# euclidean.net
KiCad netlist of a schematic drawn in EAGLE
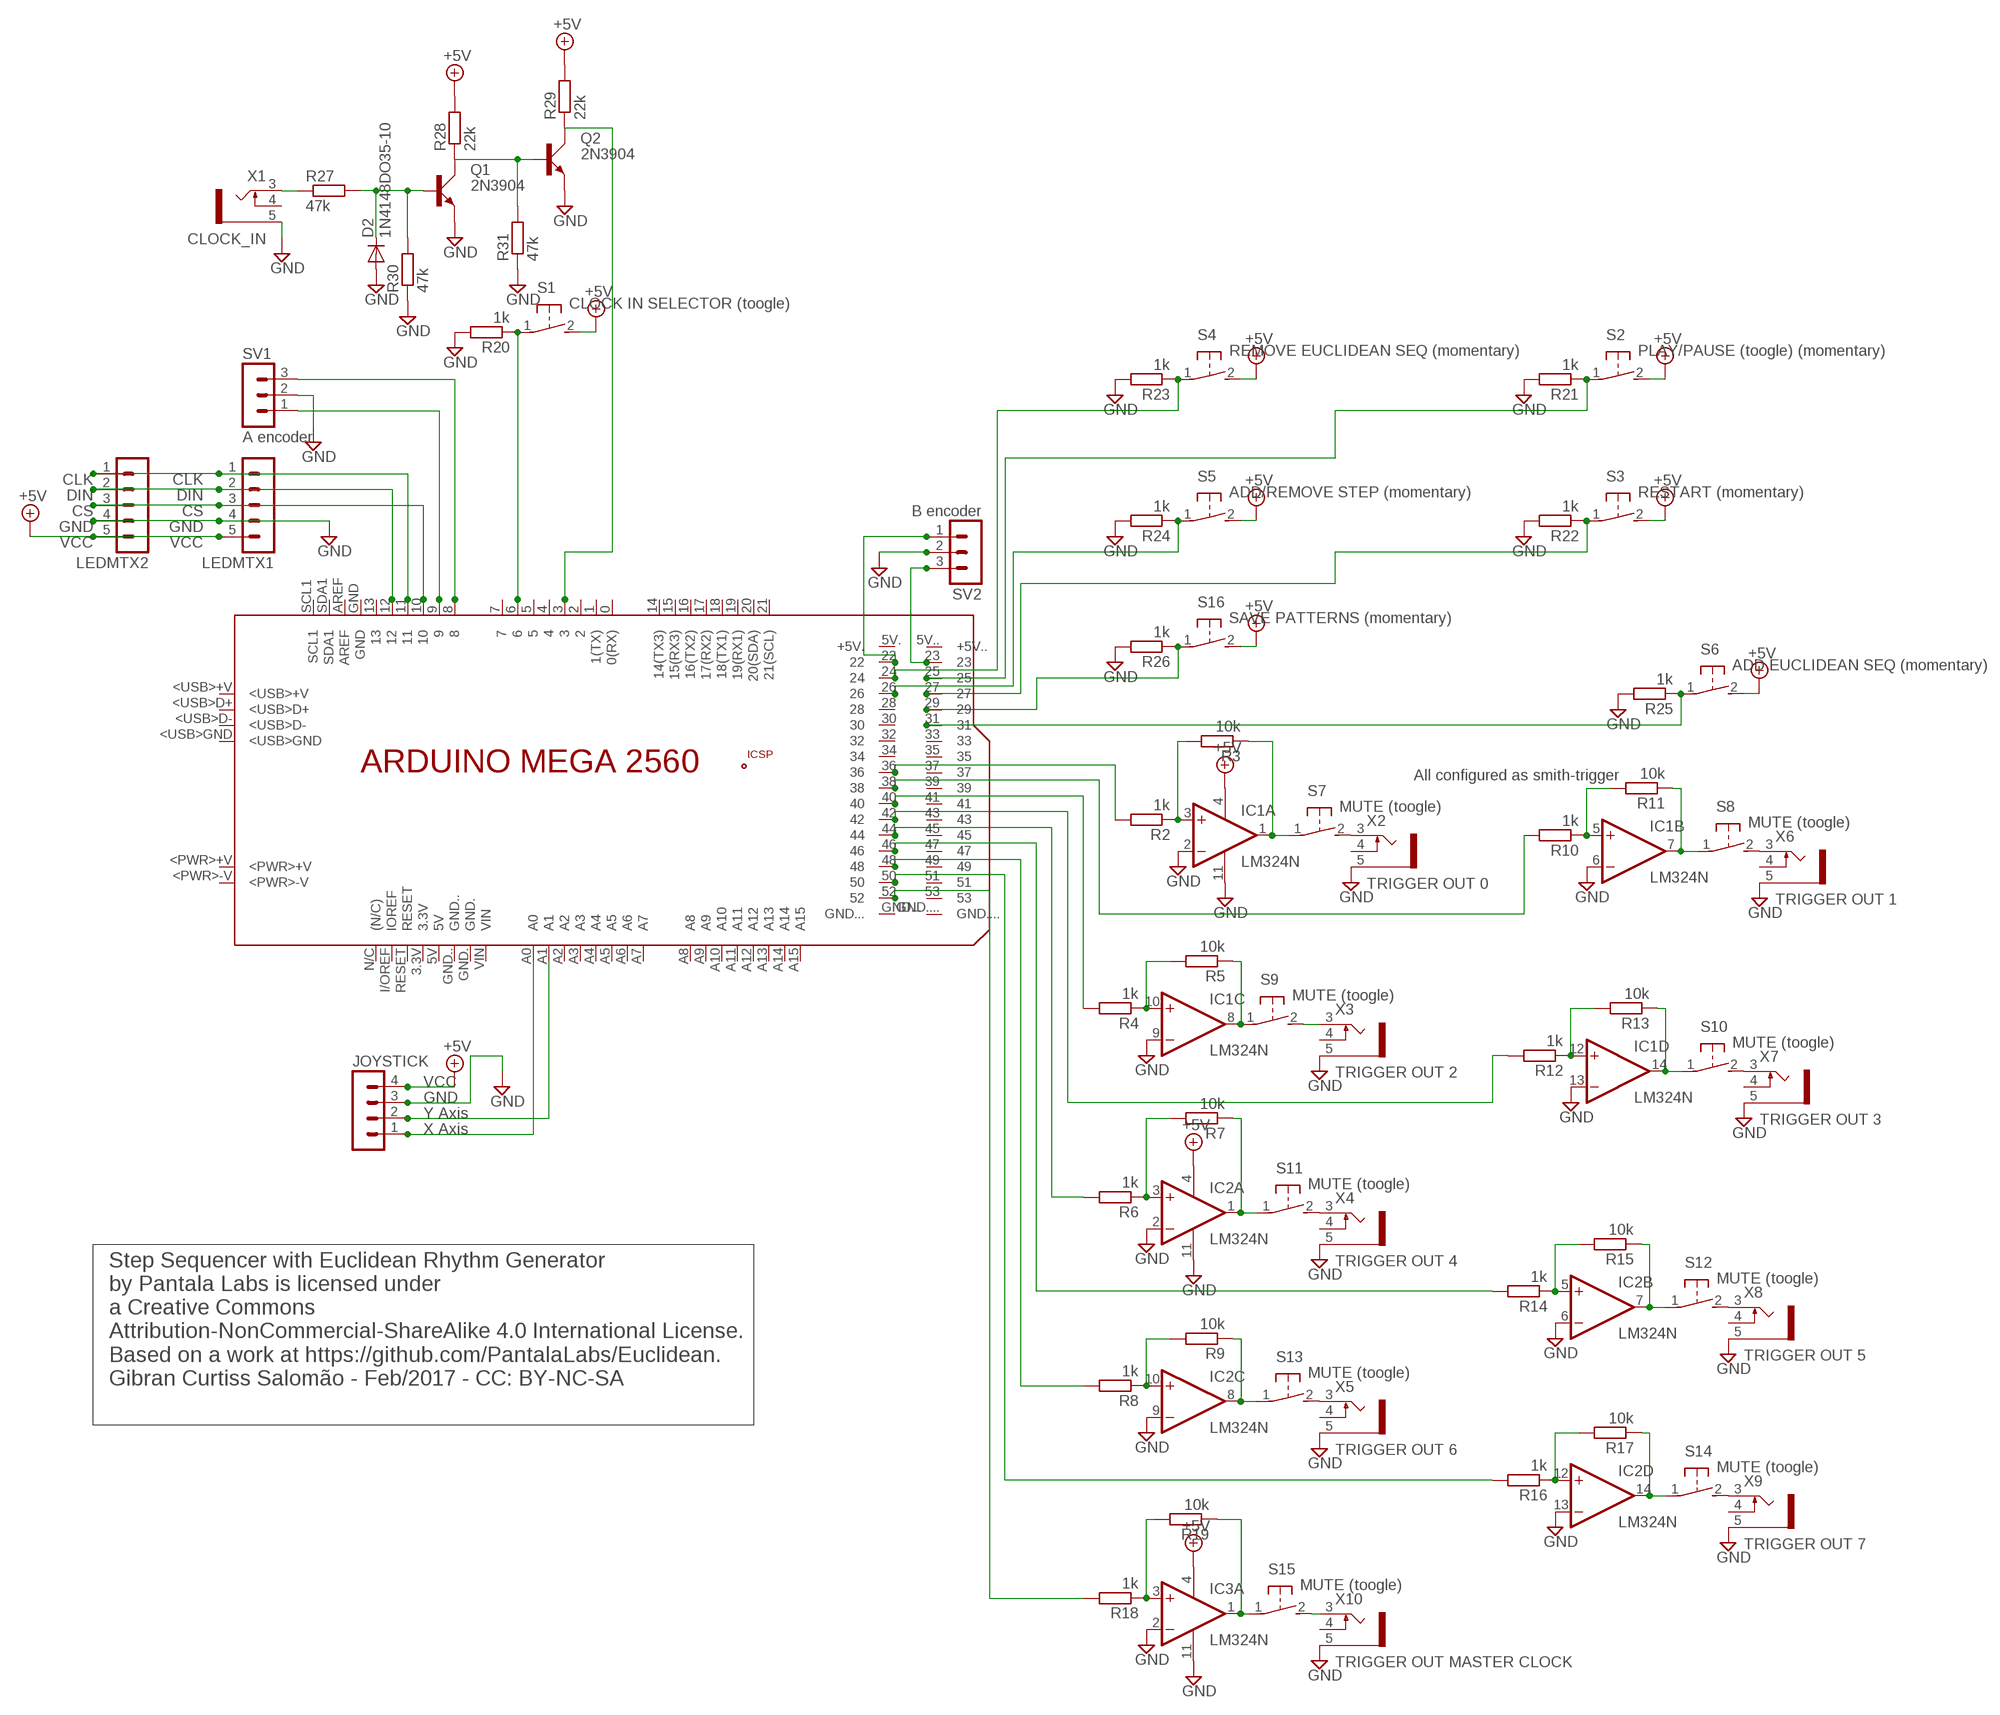
[diagram p0: schematic, sheet 1]

(export (version "E")
  (design (tool "Eeschema 10.0.6"))
  (components
    (comp (ref "D2")
      (value "1N4148DO35-10")
      (footprint "eagle-import:DO35-10")
      (libsource (lib "eagle-import") (part "1N4148DO35-10"))
    )
    (comp (ref "IC1")
      (value "LM324N")
      (footprint "eagle-import:DIL14")
      (libsource (lib "eagle-import") (part "LM324N"))
    )
    (comp (ref "IC2")
      (value "LM324N")
      (footprint "eagle-import:DIL14")
      (libsource (lib "eagle-import") (part "LM324N"))
    )
    (comp (ref "IC3")
      (value "LM324N")
      (footprint "eagle-import:DIL14")
      (libsource (lib "eagle-import") (part "LM324N"))
    )
    (comp (ref "JOYSTICK")
      (value "MA04-1")
      (footprint "eagle-import:MA04-1")
      (libsource (lib "eagle-import") (part "MA04-1"))
    )
    (comp (ref "LEDMTX1")
      (value "MA05-1")
      (footprint "eagle-import:MA05-1")
      (libsource (lib "eagle-import") (part "MA05-1"))
    )
    (comp (ref "LEDMTX2")
      (value "MA05-1")
      (footprint "eagle-import:MA05-1")
      (libsource (lib "eagle-import") (part "MA05-1"))
    )
    (comp (ref "PCB1")
      (value "ARDUINO_MEGA2560")
      (footprint "eagle-import:ARDUINO_MEGA2560")
      (libsource (lib "eagle-import") (part "ARDUINO_MEGA2560"))
    )
    (comp (ref "Q1")
      (value "2N3904")
      (footprint "eagle-import:TO92D")
      (libsource (lib "eagle-import") (part "2N3904"))
    )
    (comp (ref "Q2")
      (value "2N3904")
      (footprint "eagle-import:TO92D")
      (libsource (lib "eagle-import") (part "2N3904"))
    )
    (comp (ref "R2")
      (value "1k")
      (footprint "eagle-import:0204_7")
      (libsource (lib "eagle-import") (part "R-EU_0204/7"))
    )
    (comp (ref "R3")
      (value "10k")
      (footprint "eagle-import:0204_7")
      (libsource (lib "eagle-import") (part "R-EU_0204/7"))
    )
    (comp (ref "R4")
      (value "1k")
      (footprint "eagle-import:0204_7")
      (libsource (lib "eagle-import") (part "R-EU_0204/7"))
    )
    (comp (ref "R5")
      (value "10k")
      (footprint "eagle-import:0204_7")
      (libsource (lib "eagle-import") (part "R-EU_0204/7"))
    )
    (comp (ref "R6")
      (value "1k")
      (footprint "eagle-import:0204_7")
      (libsource (lib "eagle-import") (part "R-EU_0204/7"))
    )
    (comp (ref "R7")
      (value "10k")
      (footprint "eagle-import:0204_7")
      (libsource (lib "eagle-import") (part "R-EU_0204/7"))
    )
    (comp (ref "R8")
      (value "1k")
      (footprint "eagle-import:0204_7")
      (libsource (lib "eagle-import") (part "R-EU_0204/7"))
    )
    (comp (ref "R9")
      (value "10k")
      (footprint "eagle-import:0204_7")
      (libsource (lib "eagle-import") (part "R-EU_0204/7"))
    )
    (comp (ref "R10")
      (value "1k")
      (footprint "eagle-import:0204_7")
      (libsource (lib "eagle-import") (part "R-EU_0204/7"))
    )
    (comp (ref "R11")
      (value "10k")
      (footprint "eagle-import:0204_7")
      (libsource (lib "eagle-import") (part "R-EU_0204/7"))
    )
    (comp (ref "R12")
      (value "1k")
      (footprint "eagle-import:0204_7")
      (libsource (lib "eagle-import") (part "R-EU_0204/7"))
    )
    (comp (ref "R13")
      (value "10k")
      (footprint "eagle-import:0204_7")
      (libsource (lib "eagle-import") (part "R-EU_0204/7"))
    )
    (comp (ref "R14")
      (value "1k")
      (footprint "eagle-import:0204_7")
      (libsource (lib "eagle-import") (part "R-EU_0204/7"))
    )
    (comp (ref "R15")
      (value "10k")
      (footprint "eagle-import:0204_7")
      (libsource (lib "eagle-import") (part "R-EU_0204/7"))
    )
    (comp (ref "R16")
      (value "1k")
      (footprint "eagle-import:0204_7")
      (libsource (lib "eagle-import") (part "R-EU_0204/7"))
    )
    (comp (ref "R17")
      (value "10k")
      (footprint "eagle-import:0204_7")
      (libsource (lib "eagle-import") (part "R-EU_0204/7"))
    )
    (comp (ref "R18")
      (value "1k")
      (footprint "eagle-import:0204_7")
      (libsource (lib "eagle-import") (part "R-EU_0204/7"))
    )
    (comp (ref "R19")
      (value "10k")
      (footprint "eagle-import:0204_7")
      (libsource (lib "eagle-import") (part "R-EU_0204/7"))
    )
    (comp (ref "R20")
      (value "1k")
      (footprint "eagle-import:0204_7")
      (libsource (lib "eagle-import") (part "R-EU_0204/7"))
    )
    (comp (ref "R21")
      (value "1k")
      (footprint "eagle-import:0204_7")
      (libsource (lib "eagle-import") (part "R-EU_0204/7"))
    )
    (comp (ref "R22")
      (value "1k")
      (footprint "eagle-import:0204_7")
      (libsource (lib "eagle-import") (part "R-EU_0204/7"))
    )
    (comp (ref "R23")
      (value "1k")
      (footprint "eagle-import:0204_7")
      (libsource (lib "eagle-import") (part "R-EU_0204/7"))
    )
    (comp (ref "R24")
      (value "1k")
      (footprint "eagle-import:0204_7")
      (libsource (lib "eagle-import") (part "R-EU_0204/7"))
    )
    (comp (ref "R25")
      (value "1k")
      (footprint "eagle-import:0204_7")
      (libsource (lib "eagle-import") (part "R-EU_0204/7"))
    )
    (comp (ref "R26")
      (value "1k")
      (footprint "eagle-import:0204_7")
      (libsource (lib "eagle-import") (part "R-EU_0204/7"))
    )
    (comp (ref "R27")
      (value "47k")
      (footprint "eagle-import:0204_7")
      (libsource (lib "eagle-import") (part "R-EU_0204/7"))
    )
    (comp (ref "R28")
      (value "22k")
      (footprint "eagle-import:0204_7")
      (libsource (lib "eagle-import") (part "R-EU_0204/7"))
    )
    (comp (ref "R29")
      (value "22k")
      (footprint "eagle-import:0204_7")
      (libsource (lib "eagle-import") (part "R-EU_0204/7"))
    )
    (comp (ref "R30")
      (value "47k")
      (footprint "eagle-import:0204_7")
      (libsource (lib "eagle-import") (part "R-EU_0204/7"))
    )
    (comp (ref "R31")
      (value "47k")
      (footprint "eagle-import:0204_7")
      (libsource (lib "eagle-import") (part "R-EU_0204/7"))
    )
    (comp (ref "S1")
      (value "CLOCK IN SELECTOR (toogle)")
      (footprint "eagle-import:B3F-31XX")
      (fields (field (name "MPN") "B3F-3100"))
      (libsource (lib "eagle-import") (part "31-XX"))
    )
    (comp (ref "S2")
      (value "PLAY/PAUSE (toogle) (momentary)")
      (footprint "eagle-import:B3F-31XX")
      (fields (field (name "MPN") "B3F-3100"))
      (libsource (lib "eagle-import") (part "31-XX"))
    )
    (comp (ref "S3")
      (value "RESTART (momentary)")
      (footprint "eagle-import:B3F-31XX")
      (fields (field (name "MPN") "B3F-3100"))
      (libsource (lib "eagle-import") (part "31-XX"))
    )
    (comp (ref "S4")
      (value "REMOVE EUCLIDEAN SEQ (momentary)")
      (footprint "eagle-import:B3F-31XX")
      (fields (field (name "MPN") "B3F-3100"))
      (libsource (lib "eagle-import") (part "31-XX"))
    )
    (comp (ref "S5")
      (value "ADD/REMOVE STEP (momentary)")
      (footprint "eagle-import:B3F-31XX")
      (fields (field (name "MPN") "B3F-3100"))
      (libsource (lib "eagle-import") (part "31-XX"))
    )
    (comp (ref "S6")
      (value "ADD EUCLIDEAN SEQ (momentary)")
      (footprint "eagle-import:B3F-31XX")
      (fields (field (name "MPN") "B3F-3100"))
      (libsource (lib "eagle-import") (part "31-XX"))
    )
    (comp (ref "S7")
      (value "MUTE (toogle)")
      (footprint "eagle-import:B3F-31XX")
      (fields (field (name "MPN") "B3F-3100"))
      (libsource (lib "eagle-import") (part "31-XX"))
    )
    (comp (ref "S8")
      (value "MUTE (toogle)")
      (footprint "eagle-import:B3F-31XX")
      (fields (field (name "MPN") "B3F-3100"))
      (libsource (lib "eagle-import") (part "31-XX"))
    )
    (comp (ref "S9")
      (value "MUTE (toogle)")
      (footprint "eagle-import:B3F-31XX")
      (fields (field (name "MPN") "B3F-3100"))
      (libsource (lib "eagle-import") (part "31-XX"))
    )
    (comp (ref "S10")
      (value "MUTE (toogle)")
      (footprint "eagle-import:B3F-31XX")
      (fields (field (name "MPN") "B3F-3100"))
      (libsource (lib "eagle-import") (part "31-XX"))
    )
    (comp (ref "S11")
      (value "MUTE (toogle)")
      (footprint "eagle-import:B3F-31XX")
      (fields (field (name "MPN") "B3F-3100"))
      (libsource (lib "eagle-import") (part "31-XX"))
    )
    (comp (ref "S12")
      (value "MUTE (toogle)")
      (footprint "eagle-import:B3F-31XX")
      (fields (field (name "MPN") "B3F-3100"))
      (libsource (lib "eagle-import") (part "31-XX"))
    )
    (comp (ref "S13")
      (value "MUTE (toogle)")
      (footprint "eagle-import:B3F-31XX")
      (fields (field (name "MPN") "B3F-3100"))
      (libsource (lib "eagle-import") (part "31-XX"))
    )
    (comp (ref "S14")
      (value "MUTE (toogle)")
      (footprint "eagle-import:B3F-31XX")
      (fields (field (name "MPN") "B3F-3100"))
      (libsource (lib "eagle-import") (part "31-XX"))
    )
    (comp (ref "S15")
      (value "MUTE (toogle)")
      (footprint "eagle-import:B3F-31XX")
      (fields (field (name "MPN") "B3F-3100"))
      (libsource (lib "eagle-import") (part "31-XX"))
    )
    (comp (ref "S16")
      (value "SAVE PATTERNS (momentary)")
      (footprint "eagle-import:B3F-31XX")
      (fields (field (name "MPN") "B3F-3100"))
      (libsource (lib "eagle-import") (part "31-XX"))
    )
    (comp (ref "SV1")
      (value "A encoder")
      (footprint "eagle-import:MA03-1")
      (libsource (lib "eagle-import") (part "MA03-1"))
    )
    (comp (ref "SV2")
      (value "B encoder")
      (footprint "eagle-import:MA03-1")
      (libsource (lib "eagle-import") (part "MA03-1"))
    )
    (comp (ref "X1")
      (value "CLOCK_IN")
      (footprint "eagle-import:KLBR1")
      (fields (field (name "MPN") "KLBR 1"))
      (libsource (lib "eagle-import") (part "KLBR?1"))
    )
    (comp (ref "X2")
      (value "TRIGGER OUT 0")
      (footprint "eagle-import:KLBR1")
      (fields (field (name "MPN") "KLBR 1"))
      (libsource (lib "eagle-import") (part "KLBR?1"))
    )
    (comp (ref "X3")
      (value "TRIGGER OUT 2")
      (footprint "eagle-import:KLBR1")
      (fields (field (name "MPN") "KLBR 1"))
      (libsource (lib "eagle-import") (part "KLBR?1"))
    )
    (comp (ref "X4")
      (value "TRIGGER OUT 4")
      (footprint "eagle-import:KLBR1")
      (fields (field (name "MPN") "KLBR 1"))
      (libsource (lib "eagle-import") (part "KLBR?1"))
    )
    (comp (ref "X5")
      (value "TRIGGER OUT 6")
      (footprint "eagle-import:KLBR1")
      (fields (field (name "MPN") "KLBR 1"))
      (libsource (lib "eagle-import") (part "KLBR?1"))
    )
    (comp (ref "X6")
      (value "TRIGGER OUT 1")
      (footprint "eagle-import:KLBR1")
      (fields (field (name "MPN") "KLBR 1"))
      (libsource (lib "eagle-import") (part "KLBR?1"))
    )
    (comp (ref "X7")
      (value "TRIGGER OUT 3")
      (footprint "eagle-import:KLBR1")
      (fields (field (name "MPN") "KLBR 1"))
      (libsource (lib "eagle-import") (part "KLBR?1"))
    )
    (comp (ref "X8")
      (value "TRIGGER OUT 5")
      (footprint "eagle-import:KLBR1")
      (fields (field (name "MPN") "KLBR 1"))
      (libsource (lib "eagle-import") (part "KLBR?1"))
    )
    (comp (ref "X9")
      (value "TRIGGER OUT 7")
      (footprint "eagle-import:KLBR1")
      (fields (field (name "MPN") "KLBR 1"))
      (libsource (lib "eagle-import") (part "KLBR?1"))
    )
    (comp (ref "X10")
      (value "TRIGGER OUT MASTER CLOCK")
      (footprint "eagle-import:KLBR1")
      (fields (field (name "MPN") "KLBR 1"))
      (libsource (lib "eagle-import") (part "KLBR?1"))
    )
  )
  (nets
    (net (code "1") (name "+5V") (class "Default")
      (node (ref "IC1") (pin "4") (pinfunction "V+_4") (pintype "power_in"))
      (node (ref "IC2") (pin "4") (pinfunction "V+_4") (pintype "power_in"))
      (node (ref "IC3") (pin "4") (pinfunction "V+_4") (pintype "power_in"))
      (node (ref "JOYSTICK") (pin "4") (pinfunction "4_4") (pintype "passive"))
      (node (ref "LEDMTX1") (pin "5") (pinfunction "5_5") (pintype "passive"))
      (node (ref "LEDMTX2") (pin "5") (pinfunction "5_5") (pintype "passive"))
      (node (ref "R28") (pin "2") (pinfunction "2_2") (pintype "passive"))
      (node (ref "R29") (pin "2") (pinfunction "2_2") (pintype "passive"))
      (node (ref "S1") (pin "2") (pinfunction "S_2") (pintype "passive"))
      (node (ref "S16") (pin "2") (pinfunction "S_2") (pintype "passive"))
      (node (ref "S2") (pin "2") (pinfunction "S_2") (pintype "passive"))
      (node (ref "S3") (pin "2") (pinfunction "S_2") (pintype "passive"))
      (node (ref "S4") (pin "2") (pinfunction "S_2") (pintype "passive"))
      (node (ref "S5") (pin "2") (pinfunction "S_2") (pintype "passive"))
      (node (ref "S6") (pin "2") (pinfunction "S_2") (pintype "passive"))
    )
    (net (code "2") (name "GND") (class "Default")
      (node (ref "D2") (pin "A") (pinfunction "A_A") (pintype "passive"))
      (node (ref "IC1") (pin "11") (pinfunction "V-_11") (pintype "power_in"))
      (node (ref "IC1") (pin "13") (pinfunction "-IN_13") (pintype "input"))
      (node (ref "IC1") (pin "2") (pinfunction "-IN_2") (pintype "input"))
      (node (ref "IC1") (pin "6") (pinfunction "-IN_6") (pintype "input"))
      (node (ref "IC1") (pin "9") (pinfunction "-IN_9") (pintype "input"))
      (node (ref "IC2") (pin "11") (pinfunction "V-_11") (pintype "power_in"))
      (node (ref "IC2") (pin "13") (pinfunction "-IN_13") (pintype "input"))
      (node (ref "IC2") (pin "2") (pinfunction "-IN_2") (pintype "input"))
      (node (ref "IC2") (pin "6") (pinfunction "-IN_6") (pintype "input"))
      (node (ref "IC2") (pin "9") (pinfunction "-IN_9") (pintype "input"))
      (node (ref "IC3") (pin "11") (pinfunction "V-_11") (pintype "power_in"))
      (node (ref "IC3") (pin "2") (pinfunction "-IN_2") (pintype "input"))
      (node (ref "JOYSTICK") (pin "3") (pinfunction "3_3") (pintype "passive"))
      (node (ref "LEDMTX1") (pin "4") (pinfunction "4_4") (pintype "passive"))
      (node (ref "LEDMTX2") (pin "4") (pinfunction "4_4") (pintype "passive"))
      (node (ref "Q1") (pin "E") (pinfunction "E_E") (pintype "passive"))
      (node (ref "Q2") (pin "E") (pinfunction "E_E") (pintype "passive"))
      (node (ref "R20") (pin "2") (pinfunction "2_2") (pintype "passive"))
      (node (ref "R21") (pin "2") (pinfunction "2_2") (pintype "passive"))
      (node (ref "R22") (pin "2") (pinfunction "2_2") (pintype "passive"))
      (node (ref "R23") (pin "2") (pinfunction "2_2") (pintype "passive"))
      (node (ref "R24") (pin "2") (pinfunction "2_2") (pintype "passive"))
      (node (ref "R25") (pin "2") (pinfunction "2_2") (pintype "passive"))
      (node (ref "R26") (pin "2") (pinfunction "2_2") (pintype "passive"))
      (node (ref "R30") (pin "1") (pinfunction "1_1") (pintype "passive"))
      (node (ref "R31") (pin "1") (pinfunction "1_1") (pintype "passive"))
      (node (ref "SV1") (pin "2") (pinfunction "2_2") (pintype "passive"))
      (node (ref "SV2") (pin "2") (pinfunction "2_2") (pintype "passive"))
      (node (ref "X1") (pin "5") (pinfunction "5_5") (pintype "passive"))
      (node (ref "X10") (pin "5") (pinfunction "5_5") (pintype "passive"))
      (node (ref "X2") (pin "5") (pinfunction "5_5") (pintype "passive"))
      (node (ref "X3") (pin "5") (pinfunction "5_5") (pintype "passive"))
      (node (ref "X4") (pin "5") (pinfunction "5_5") (pintype "passive"))
      (node (ref "X5") (pin "5") (pinfunction "5_5") (pintype "passive"))
      (node (ref "X6") (pin "5") (pinfunction "5_5") (pintype "passive"))
      (node (ref "X7") (pin "5") (pinfunction "5_5") (pintype "passive"))
      (node (ref "X8") (pin "5") (pinfunction "5_5") (pintype "passive"))
      (node (ref "X9") (pin "5") (pinfunction "5_5") (pintype "passive"))
    )
    (net (code "3") (name "Net-(D2-PadC)") (class "Default")
      (node (ref "D2") (pin "C") (pinfunction "C_C") (pintype "passive"))
      (node (ref "Q1") (pin "B") (pinfunction "B_B") (pintype "passive"))
      (node (ref "R27") (pin "2") (pinfunction "2_2") (pintype "passive"))
      (node (ref "R30") (pin "2") (pinfunction "2_2") (pintype "passive"))
    )
    (net (code "4") (name "Net-(IC1A-+IN)") (class "Default")
      (node (ref "IC1") (pin "3") (pinfunction "+IN_3") (pintype "input"))
      (node (ref "R2") (pin "1") (pinfunction "1_1") (pintype "passive"))
      (node (ref "R3") (pin "2") (pinfunction "2_2") (pintype "passive"))
    )
    (net (code "5") (name "Net-(IC1A-OUT)") (class "Default")
      (node (ref "IC1") (pin "1") (pinfunction "OUT_1") (pintype "output"))
      (node (ref "R3") (pin "1") (pinfunction "1_1") (pintype "passive"))
      (node (ref "S7") (pin "1") (pinfunction "P_1") (pintype "passive"))
    )
    (net (code "6") (name "Net-(IC1B-+IN)") (class "Default")
      (node (ref "IC1") (pin "5") (pinfunction "+IN_5") (pintype "input"))
      (node (ref "R10") (pin "1") (pinfunction "1_1") (pintype "passive"))
      (node (ref "R11") (pin "2") (pinfunction "2_2") (pintype "passive"))
    )
    (net (code "7") (name "Net-(IC1B-OUT)") (class "Default")
      (node (ref "IC1") (pin "7") (pinfunction "OUT_7") (pintype "output"))
      (node (ref "R11") (pin "1") (pinfunction "1_1") (pintype "passive"))
      (node (ref "S8") (pin "1") (pinfunction "P_1") (pintype "passive"))
    )
    (net (code "8") (name "Net-(IC1C-+IN)") (class "Default")
      (node (ref "IC1") (pin "10") (pinfunction "+IN_10") (pintype "input"))
      (node (ref "R4") (pin "1") (pinfunction "1_1") (pintype "passive"))
      (node (ref "R5") (pin "2") (pinfunction "2_2") (pintype "passive"))
    )
    (net (code "9") (name "Net-(IC1C-OUT)") (class "Default")
      (node (ref "IC1") (pin "8") (pinfunction "OUT_8") (pintype "output"))
      (node (ref "R5") (pin "1") (pinfunction "1_1") (pintype "passive"))
      (node (ref "S9") (pin "1") (pinfunction "P_1") (pintype "passive"))
    )
    (net (code "10") (name "Net-(IC1D-+IN)") (class "Default")
      (node (ref "IC1") (pin "12") (pinfunction "+IN_12") (pintype "input"))
      (node (ref "R12") (pin "1") (pinfunction "1_1") (pintype "passive"))
      (node (ref "R13") (pin "2") (pinfunction "2_2") (pintype "passive"))
    )
    (net (code "11") (name "Net-(IC1D-OUT)") (class "Default")
      (node (ref "IC1") (pin "14") (pinfunction "OUT_14") (pintype "output"))
      (node (ref "R13") (pin "1") (pinfunction "1_1") (pintype "passive"))
      (node (ref "S10") (pin "1") (pinfunction "P_1") (pintype "passive"))
    )
    (net (code "12") (name "Net-(IC2A-+IN)") (class "Default")
      (node (ref "IC2") (pin "3") (pinfunction "+IN_3") (pintype "input"))
      (node (ref "R6") (pin "1") (pinfunction "1_1") (pintype "passive"))
      (node (ref "R7") (pin "2") (pinfunction "2_2") (pintype "passive"))
    )
    (net (code "13") (name "Net-(IC2A-OUT)") (class "Default")
      (node (ref "IC2") (pin "1") (pinfunction "OUT_1") (pintype "output"))
      (node (ref "R7") (pin "1") (pinfunction "1_1") (pintype "passive"))
      (node (ref "S11") (pin "1") (pinfunction "P_1") (pintype "passive"))
    )
    (net (code "14") (name "Net-(IC2B-+IN)") (class "Default")
      (node (ref "IC2") (pin "5") (pinfunction "+IN_5") (pintype "input"))
      (node (ref "R14") (pin "1") (pinfunction "1_1") (pintype "passive"))
      (node (ref "R15") (pin "2") (pinfunction "2_2") (pintype "passive"))
    )
    (net (code "15") (name "Net-(IC2B-OUT)") (class "Default")
      (node (ref "IC2") (pin "7") (pinfunction "OUT_7") (pintype "output"))
      (node (ref "R15") (pin "1") (pinfunction "1_1") (pintype "passive"))
      (node (ref "S12") (pin "1") (pinfunction "P_1") (pintype "passive"))
    )
    (net (code "16") (name "Net-(IC2C-+IN)") (class "Default")
      (node (ref "IC2") (pin "10") (pinfunction "+IN_10") (pintype "input"))
      (node (ref "R8") (pin "1") (pinfunction "1_1") (pintype "passive"))
      (node (ref "R9") (pin "2") (pinfunction "2_2") (pintype "passive"))
    )
    (net (code "17") (name "Net-(IC2C-OUT)") (class "Default")
      (node (ref "IC2") (pin "8") (pinfunction "OUT_8") (pintype "output"))
      (node (ref "R9") (pin "1") (pinfunction "1_1") (pintype "passive"))
      (node (ref "S13") (pin "1") (pinfunction "P_1") (pintype "passive"))
    )
    (net (code "18") (name "Net-(IC2D-+IN)") (class "Default")
      (node (ref "IC2") (pin "12") (pinfunction "+IN_12") (pintype "input"))
      (node (ref "R16") (pin "1") (pinfunction "1_1") (pintype "passive"))
      (node (ref "R17") (pin "2") (pinfunction "2_2") (pintype "passive"))
    )
    (net (code "19") (name "Net-(IC2D-OUT)") (class "Default")
      (node (ref "IC2") (pin "14") (pinfunction "OUT_14") (pintype "output"))
      (node (ref "R17") (pin "1") (pinfunction "1_1") (pintype "passive"))
      (node (ref "S14") (pin "1") (pinfunction "P_1") (pintype "passive"))
    )
    (net (code "20") (name "Net-(IC3A-+IN)") (class "Default")
      (node (ref "IC3") (pin "3") (pinfunction "+IN_3") (pintype "input"))
      (node (ref "R18") (pin "1") (pinfunction "1_1") (pintype "passive"))
      (node (ref "R19") (pin "2") (pinfunction "2_2") (pintype "passive"))
    )
    (net (code "21") (name "Net-(IC3A-OUT)") (class "Default")
      (node (ref "IC3") (pin "1") (pinfunction "OUT_1") (pintype "output"))
      (node (ref "R19") (pin "1") (pinfunction "1_1") (pintype "passive"))
      (node (ref "S15") (pin "1") (pinfunction "P_1") (pintype "passive"))
    )
    (net (code "22") (name "Net-(JOYSTICK-Pad1)") (class "Default")
      (node (ref "JOYSTICK") (pin "1") (pinfunction "1_1") (pintype "passive"))
      (node (ref "PCB1") (pin "A0") (pinfunction "A0_A0") (pintype "bidirectional"))
    )
    (net (code "23") (name "Net-(JOYSTICK-Pad2)") (class "Default")
      (node (ref "JOYSTICK") (pin "2") (pinfunction "2_2") (pintype "passive"))
      (node (ref "PCB1") (pin "A1") (pinfunction "A1_A1") (pintype "bidirectional"))
    )
    (net (code "24") (name "Net-(LEDMTX1-Pad1)") (class "Default")
      (node (ref "LEDMTX1") (pin "1") (pinfunction "1_1") (pintype "passive"))
      (node (ref "LEDMTX2") (pin "1") (pinfunction "1_1") (pintype "passive"))
      (node (ref "PCB1") (pin "11") (pinfunction "11_11") (pintype "bidirectional"))
    )
    (net (code "25") (name "Net-(LEDMTX1-Pad2)") (class "Default")
      (node (ref "LEDMTX1") (pin "2") (pinfunction "2_2") (pintype "passive"))
      (node (ref "LEDMTX2") (pin "2") (pinfunction "2_2") (pintype "passive"))
      (node (ref "PCB1") (pin "12") (pinfunction "12_12") (pintype "bidirectional"))
    )
    (net (code "26") (name "Net-(LEDMTX1-Pad3)") (class "Default")
      (node (ref "LEDMTX1") (pin "3") (pinfunction "3_3") (pintype "passive"))
      (node (ref "LEDMTX2") (pin "3") (pinfunction "3_3") (pintype "passive"))
      (node (ref "PCB1") (pin "10") (pinfunction "10_10") (pintype "bidirectional"))
    )
    (net (code "27") (name "Net-(PCB1-Pad3)") (class "Default")
      (node (ref "PCB1") (pin "3") (pinfunction "3_3") (pintype "bidirectional"))
      (node (ref "Q2") (pin "C") (pinfunction "C_C") (pintype "passive"))
      (node (ref "R29") (pin "1") (pinfunction "1_1") (pintype "passive"))
    )
    (net (code "28") (name "Net-(PCB1-Pad8)") (class "Default")
      (node (ref "PCB1") (pin "8") (pinfunction "8_8") (pintype "bidirectional"))
      (node (ref "SV1") (pin "3") (pinfunction "3_3") (pintype "passive"))
    )
    (net (code "29") (name "Net-(PCB1-Pad9)") (class "Default")
      (node (ref "PCB1") (pin "9") (pinfunction "9_9") (pintype "bidirectional"))
      (node (ref "SV1") (pin "1") (pinfunction "1_1") (pintype "passive"))
    )
    (net (code "30") (name "Net-(PCB1-Pad22)") (class "Default")
      (node (ref "PCB1") (pin "22") (pinfunction "22_22") (pintype "bidirectional"))
      (node (ref "SV2") (pin "1") (pinfunction "1_1") (pintype "passive"))
    )
    (net (code "31") (name "Net-(PCB1-Pad23)") (class "Default")
      (node (ref "PCB1") (pin "23") (pinfunction "23_23") (pintype "bidirectional"))
      (node (ref "SV2") (pin "3") (pinfunction "3_3") (pintype "passive"))
    )
    (net (code "32") (name "Net-(PCB1-Pad36)") (class "Default")
      (node (ref "PCB1") (pin "36") (pinfunction "36_36") (pintype "bidirectional"))
      (node (ref "R2") (pin "2") (pinfunction "2_2") (pintype "passive"))
    )
    (net (code "33") (name "Net-(PCB1-Pad38)") (class "Default")
      (node (ref "PCB1") (pin "38") (pinfunction "38_38") (pintype "bidirectional"))
      (node (ref "R10") (pin "2") (pinfunction "2_2") (pintype "passive"))
    )
    (net (code "34") (name "Net-(PCB1-Pad40)") (class "Default")
      (node (ref "PCB1") (pin "40") (pinfunction "40_40") (pintype "bidirectional"))
      (node (ref "R4") (pin "2") (pinfunction "2_2") (pintype "passive"))
    )
    (net (code "35") (name "Net-(PCB1-Pad42)") (class "Default")
      (node (ref "PCB1") (pin "42") (pinfunction "42_42") (pintype "bidirectional"))
      (node (ref "R12") (pin "2") (pinfunction "2_2") (pintype "passive"))
    )
    (net (code "36") (name "Net-(PCB1-Pad44)") (class "Default")
      (node (ref "PCB1") (pin "44") (pinfunction "44_44") (pintype "bidirectional"))
      (node (ref "R6") (pin "2") (pinfunction "2_2") (pintype "passive"))
    )
    (net (code "37") (name "Net-(PCB1-Pad46)") (class "Default")
      (node (ref "PCB1") (pin "46") (pinfunction "46_46") (pintype "bidirectional"))
      (node (ref "R14") (pin "2") (pinfunction "2_2") (pintype "passive"))
    )
    (net (code "38") (name "Net-(PCB1-Pad48)") (class "Default")
      (node (ref "PCB1") (pin "48") (pinfunction "48_48") (pintype "bidirectional"))
      (node (ref "R8") (pin "2") (pinfunction "2_2") (pintype "passive"))
    )
    (net (code "39") (name "Net-(PCB1-Pad50)") (class "Default")
      (node (ref "PCB1") (pin "50") (pinfunction "50_50") (pintype "bidirectional"))
      (node (ref "R16") (pin "2") (pinfunction "2_2") (pintype "passive"))
    )
    (net (code "40") (name "Net-(PCB1-Pad52)") (class "Default")
      (node (ref "PCB1") (pin "52") (pinfunction "52_52") (pintype "bidirectional"))
      (node (ref "R18") (pin "2") (pinfunction "2_2") (pintype "passive"))
    )
    (net (code "41") (name "Net-(Q1-PadC)") (class "Default")
      (node (ref "Q1") (pin "C") (pinfunction "C_C") (pintype "passive"))
      (node (ref "Q2") (pin "B") (pinfunction "B_B") (pintype "passive"))
      (node (ref "R28") (pin "1") (pinfunction "1_1") (pintype "passive"))
      (node (ref "R31") (pin "2") (pinfunction "2_2") (pintype "passive"))
    )
    (net (code "42") (name "Net-(R27-Pad1)") (class "Default")
      (node (ref "R27") (pin "1") (pinfunction "1_1") (pintype "passive"))
      (node (ref "X1") (pin "3") (pinfunction "3_3") (pintype "passive"))
    )
    (net (code "43") (name "Net-(S1-P)") (class "Default")
      (node (ref "PCB1") (pin "6") (pinfunction "6_6") (pintype "bidirectional"))
      (node (ref "R20") (pin "1") (pinfunction "1_1") (pintype "passive"))
      (node (ref "S1") (pin "1") (pinfunction "P_1") (pintype "passive"))
    )
    (net (code "44") (name "Net-(S2-P)") (class "Default")
      (node (ref "PCB1") (pin "25") (pinfunction "25_25") (pintype "bidirectional"))
      (node (ref "R21") (pin "1") (pinfunction "1_1") (pintype "passive"))
      (node (ref "S2") (pin "1") (pinfunction "P_1") (pintype "passive"))
    )
    (net (code "45") (name "Net-(S3-P)") (class "Default")
      (node (ref "PCB1") (pin "27") (pinfunction "27_27") (pintype "bidirectional"))
      (node (ref "R22") (pin "1") (pinfunction "1_1") (pintype "passive"))
      (node (ref "S3") (pin "1") (pinfunction "P_1") (pintype "passive"))
    )
    (net (code "46") (name "Net-(S4-P)") (class "Default")
      (node (ref "PCB1") (pin "24") (pinfunction "24_24") (pintype "bidirectional"))
      (node (ref "R23") (pin "1") (pinfunction "1_1") (pintype "passive"))
      (node (ref "S4") (pin "1") (pinfunction "P_1") (pintype "passive"))
    )
    (net (code "47") (name "Net-(S5-P)") (class "Default")
      (node (ref "PCB1") (pin "26") (pinfunction "26_26") (pintype "bidirectional"))
      (node (ref "R24") (pin "1") (pinfunction "1_1") (pintype "passive"))
      (node (ref "S5") (pin "1") (pinfunction "P_1") (pintype "passive"))
    )
    (net (code "48") (name "Net-(S6-P)") (class "Default")
      (node (ref "PCB1") (pin "31") (pinfunction "31_31") (pintype "bidirectional"))
      (node (ref "R25") (pin "1") (pinfunction "1_1") (pintype "passive"))
      (node (ref "S6") (pin "1") (pinfunction "P_1") (pintype "passive"))
    )
    (net (code "49") (name "Net-(S7-S)") (class "Default")
      (node (ref "S7") (pin "2") (pinfunction "S_2") (pintype "passive"))
      (node (ref "X2") (pin "3") (pinfunction "3_3") (pintype "passive"))
    )
    (net (code "50") (name "Net-(S8-S)") (class "Default")
      (node (ref "S8") (pin "2") (pinfunction "S_2") (pintype "passive"))
      (node (ref "X6") (pin "3") (pinfunction "3_3") (pintype "passive"))
    )
    (net (code "51") (name "Net-(S9-S)") (class "Default")
      (node (ref "S9") (pin "2") (pinfunction "S_2") (pintype "passive"))
      (node (ref "X3") (pin "3") (pinfunction "3_3") (pintype "passive"))
    )
    (net (code "52") (name "Net-(S10-S)") (class "Default")
      (node (ref "S10") (pin "2") (pinfunction "S_2") (pintype "passive"))
      (node (ref "X7") (pin "3") (pinfunction "3_3") (pintype "passive"))
    )
    (net (code "53") (name "Net-(S11-S)") (class "Default")
      (node (ref "S11") (pin "2") (pinfunction "S_2") (pintype "passive"))
      (node (ref "X4") (pin "3") (pinfunction "3_3") (pintype "passive"))
    )
    (net (code "54") (name "Net-(S12-S)") (class "Default")
      (node (ref "S12") (pin "2") (pinfunction "S_2") (pintype "passive"))
      (node (ref "X8") (pin "3") (pinfunction "3_3") (pintype "passive"))
    )
    (net (code "55") (name "Net-(S13-S)") (class "Default")
      (node (ref "S13") (pin "2") (pinfunction "S_2") (pintype "passive"))
      (node (ref "X5") (pin "3") (pinfunction "3_3") (pintype "passive"))
    )
    (net (code "56") (name "Net-(S14-S)") (class "Default")
      (node (ref "S14") (pin "2") (pinfunction "S_2") (pintype "passive"))
      (node (ref "X9") (pin "3") (pinfunction "3_3") (pintype "passive"))
    )
    (net (code "57") (name "Net-(S15-S)") (class "Default")
      (node (ref "S15") (pin "2") (pinfunction "S_2") (pintype "passive"))
      (node (ref "X10") (pin "3") (pinfunction "3_3") (pintype "passive"))
    )
    (net (code "58") (name "Net-(S16-P)") (class "Default")
      (node (ref "PCB1") (pin "29") (pinfunction "29_29") (pintype "bidirectional"))
      (node (ref "R26") (pin "1") (pinfunction "1_1") (pintype "passive"))
      (node (ref "S16") (pin "1") (pinfunction "P_1") (pintype "passive"))
    )
    (net (code "59") (name "unconnected-(PCB1-(N{slash}C)-PadN{slash}C)") (class "Default")
      (node (ref "PCB1") (pin "N/C") (pinfunction "(N/C)_N/C") (pintype "bidirectional"))
    )
    (net (code "60") (name "unconnected-(PCB1-+5V.-Pad5V.)") (class "Default")
      (node (ref "PCB1") (pin "5V.") (pinfunction "+5V._5V.") (pintype "bidirectional"))
    )
    (net (code "61") (name "unconnected-(PCB1-+5V..-Pad5V..)") (class "Default")
      (node (ref "PCB1") (pin "5V..") (pinfunction "+5V.._5V..") (pintype "bidirectional"))
    )
    (net (code "62") (name "unconnected-(PCB1-0(RX)-Pad0)") (class "Default")
      (node (ref "PCB1") (pin "0") (pinfunction "0(RX)_0") (pintype "bidirectional"))
    )
    (net (code "63") (name "unconnected-(PCB1-1(TX)-Pad1)") (class "Default")
      (node (ref "PCB1") (pin "1") (pinfunction "1(TX)_1") (pintype "bidirectional"))
    )
    (net (code "64") (name "unconnected-(PCB1-14(TX3)-Pad14)") (class "Default")
      (node (ref "PCB1") (pin "14") (pinfunction "14(TX3)_14") (pintype "bidirectional"))
    )
    (net (code "65") (name "unconnected-(PCB1-15(RX3)-Pad15)") (class "Default")
      (node (ref "PCB1") (pin "15") (pinfunction "15(RX3)_15") (pintype "bidirectional"))
    )
    (net (code "66") (name "unconnected-(PCB1-16(TX2)-Pad16)") (class "Default")
      (node (ref "PCB1") (pin "16") (pinfunction "16(TX2)_16") (pintype "bidirectional"))
    )
    (net (code "67") (name "unconnected-(PCB1-17(RX2)-Pad17)") (class "Default")
      (node (ref "PCB1") (pin "17") (pinfunction "17(RX2)_17") (pintype "bidirectional"))
    )
    (net (code "68") (name "unconnected-(PCB1-18(TX1)-Pad18)") (class "Default")
      (node (ref "PCB1") (pin "18") (pinfunction "18(TX1)_18") (pintype "bidirectional"))
    )
    (net (code "69") (name "unconnected-(PCB1-19(RX1)-Pad19)") (class "Default")
      (node (ref "PCB1") (pin "19") (pinfunction "19(RX1)_19") (pintype "bidirectional"))
    )
    (net (code "70") (name "unconnected-(PCB1-20(SDA)-Pad20)") (class "Default")
      (node (ref "PCB1") (pin "20") (pinfunction "20(SDA)_20") (pintype "bidirectional"))
    )
    (net (code "71") (name "unconnected-(PCB1-21(SCL)-Pad21)") (class "Default")
      (node (ref "PCB1") (pin "21") (pinfunction "21(SCL)_21") (pintype "bidirectional"))
    )
    (net (code "72") (name "unconnected-(PCB1-IOREF-PadI{slash}OREF)") (class "Default")
      (node (ref "PCB1") (pin "I/OREF") (pinfunction "IOREF_I/OREF") (pintype "bidirectional"))
    )
    (net (code "73") (name "unconnected-(PCB1-Pad+5V_)") (class "Default")
      (node (ref "PCB1") (pin "+5V_") (pinfunction "+5V__+5V_") (pintype "bidirectional"))
    )
    (net (code "74") (name "unconnected-(PCB1-Pad2)") (class "Default")
      (node (ref "PCB1") (pin "2") (pinfunction "2_2") (pintype "bidirectional"))
    )
    (net (code "75") (name "unconnected-(PCB1-Pad3.3V)") (class "Default")
      (node (ref "PCB1") (pin "3.3V") (pinfunction "3.3V_3.3V") (pintype "bidirectional"))
    )
    (net (code "76") (name "unconnected-(PCB1-Pad4)") (class "Default")
      (node (ref "PCB1") (pin "4") (pinfunction "4_4") (pintype "bidirectional"))
    )
    (net (code "77") (name "unconnected-(PCB1-Pad5)") (class "Default")
      (node (ref "PCB1") (pin "5") (pinfunction "5_5") (pintype "bidirectional"))
    )
    (net (code "78") (name "unconnected-(PCB1-Pad5V)") (class "Default")
      (node (ref "PCB1") (pin "5V") (pinfunction "5V_5V") (pintype "bidirectional"))
    )
    (net (code "79") (name "unconnected-(PCB1-Pad7)") (class "Default")
      (node (ref "PCB1") (pin "7") (pinfunction "7_7") (pintype "bidirectional"))
    )
    (net (code "80") (name "unconnected-(PCB1-Pad13)") (class "Default")
      (node (ref "PCB1") (pin "13") (pinfunction "13_13") (pintype "bidirectional"))
    )
    (net (code "81") (name "unconnected-(PCB1-Pad28)") (class "Default")
      (node (ref "PCB1") (pin "28") (pinfunction "28_28") (pintype "bidirectional"))
    )
    (net (code "82") (name "unconnected-(PCB1-Pad30)") (class "Default")
      (node (ref "PCB1") (pin "30") (pinfunction "30_30") (pintype "bidirectional"))
    )
    (net (code "83") (name "unconnected-(PCB1-Pad32)") (class "Default")
      (node (ref "PCB1") (pin "32") (pinfunction "32_32") (pintype "bidirectional"))
    )
    (net (code "84") (name "unconnected-(PCB1-Pad33)") (class "Default")
      (node (ref "PCB1") (pin "33") (pinfunction "33_33") (pintype "bidirectional"))
    )
    (net (code "85") (name "unconnected-(PCB1-Pad34)") (class "Default")
      (node (ref "PCB1") (pin "34") (pinfunction "34_34") (pintype "bidirectional"))
    )
    (net (code "86") (name "unconnected-(PCB1-Pad35)") (class "Default")
      (node (ref "PCB1") (pin "35") (pinfunction "35_35") (pintype "bidirectional"))
    )
    (net (code "87") (name "unconnected-(PCB1-Pad37)") (class "Default")
      (node (ref "PCB1") (pin "37") (pinfunction "37_37") (pintype "bidirectional"))
    )
    (net (code "88") (name "unconnected-(PCB1-Pad39)") (class "Default")
      (node (ref "PCB1") (pin "39") (pinfunction "39_39") (pintype "bidirectional"))
    )
    (net (code "89") (name "unconnected-(PCB1-Pad41)") (class "Default")
      (node (ref "PCB1") (pin "41") (pinfunction "41_41") (pintype "bidirectional"))
    )
    (net (code "90") (name "unconnected-(PCB1-Pad43)") (class "Default")
      (node (ref "PCB1") (pin "43") (pinfunction "43_43") (pintype "bidirectional"))
    )
    (net (code "91") (name "unconnected-(PCB1-Pad45)") (class "Default")
      (node (ref "PCB1") (pin "45") (pinfunction "45_45") (pintype "bidirectional"))
    )
    (net (code "92") (name "unconnected-(PCB1-Pad47)") (class "Default")
      (node (ref "PCB1") (pin "47") (pinfunction "47_47") (pintype "bidirectional"))
    )
    (net (code "93") (name "unconnected-(PCB1-Pad49)") (class "Default")
      (node (ref "PCB1") (pin "49") (pinfunction "49_49") (pintype "bidirectional"))
    )
    (net (code "94") (name "unconnected-(PCB1-Pad51)") (class "Default")
      (node (ref "PCB1") (pin "51") (pinfunction "51_51") (pintype "bidirectional"))
    )
    (net (code "95") (name "unconnected-(PCB1-Pad53)") (class "Default")
      (node (ref "PCB1") (pin "53") (pinfunction "53_53") (pintype "bidirectional"))
    )
    (net (code "96") (name "unconnected-(PCB1-Pad<PWR>+V)") (class "Default")
      (node (ref "PCB1") (pin "<PWR>+V") (pinfunction "<PWR>+V_<PWR>+V") (pintype "no_connect"))
    )
    (net (code "97") (name "unconnected-(PCB1-Pad<PWR>-V)") (class "Default")
      (node (ref "PCB1") (pin "<PWR>-V") (pinfunction "<PWR>-V_<PWR>-V") (pintype "no_connect"))
    )
    (net (code "98") (name "unconnected-(PCB1-Pad<USB>+V)") (class "Default")
      (node (ref "PCB1") (pin "<USB>+V") (pinfunction "<USB>+V_<USB>+V") (pintype "no_connect"))
    )
    (net (code "99") (name "unconnected-(PCB1-Pad<USB>D+)") (class "Default")
      (node (ref "PCB1") (pin "<USB>D+") (pinfunction "<USB>D+_<USB>D+") (pintype "no_connect"))
    )
    (net (code "100") (name "unconnected-(PCB1-Pad<USB>D-)") (class "Default")
      (node (ref "PCB1") (pin "<USB>D-") (pinfunction "<USB>D-_<USB>D-") (pintype "no_connect"))
    )
    (net (code "101") (name "unconnected-(PCB1-Pad<USB>GND)") (class "Default")
      (node (ref "PCB1") (pin "<USB>GND") (pinfunction "<USB>GND_<USB>GND") (pintype "no_connect"))
    )
    (net (code "102") (name "unconnected-(PCB1-PadA2)") (class "Default")
      (node (ref "PCB1") (pin "A2") (pinfunction "A2_A2") (pintype "bidirectional"))
    )
    (net (code "103") (name "unconnected-(PCB1-PadA3)") (class "Default")
      (node (ref "PCB1") (pin "A3") (pinfunction "A3_A3") (pintype "bidirectional"))
    )
    (net (code "104") (name "unconnected-(PCB1-PadA4)") (class "Default")
      (node (ref "PCB1") (pin "A4") (pinfunction "A4_A4") (pintype "bidirectional"))
    )
    (net (code "105") (name "unconnected-(PCB1-PadA5)") (class "Default")
      (node (ref "PCB1") (pin "A5") (pinfunction "A5_A5") (pintype "bidirectional"))
    )
    (net (code "106") (name "unconnected-(PCB1-PadA6)") (class "Default")
      (node (ref "PCB1") (pin "A6") (pinfunction "A6_A6") (pintype "bidirectional"))
    )
    (net (code "107") (name "unconnected-(PCB1-PadA7)") (class "Default")
      (node (ref "PCB1") (pin "A7") (pinfunction "A7_A7") (pintype "bidirectional"))
    )
    (net (code "108") (name "unconnected-(PCB1-PadA8)") (class "Default")
      (node (ref "PCB1") (pin "A8") (pinfunction "A8_A8") (pintype "bidirectional"))
    )
    (net (code "109") (name "unconnected-(PCB1-PadA9)") (class "Default")
      (node (ref "PCB1") (pin "A9") (pinfunction "A9_A9") (pintype "bidirectional"))
    )
    (net (code "110") (name "unconnected-(PCB1-PadA10)") (class "Default")
      (node (ref "PCB1") (pin "A10") (pinfunction "A10_A10") (pintype "bidirectional"))
    )
    (net (code "111") (name "unconnected-(PCB1-PadA11)") (class "Default")
      (node (ref "PCB1") (pin "A11") (pinfunction "A11_A11") (pintype "bidirectional"))
    )
    (net (code "112") (name "unconnected-(PCB1-PadA12)") (class "Default")
      (node (ref "PCB1") (pin "A12") (pinfunction "A12_A12") (pintype "bidirectional"))
    )
    (net (code "113") (name "unconnected-(PCB1-PadA13)") (class "Default")
      (node (ref "PCB1") (pin "A13") (pinfunction "A13_A13") (pintype "bidirectional"))
    )
    (net (code "114") (name "unconnected-(PCB1-PadA14)") (class "Default")
      (node (ref "PCB1") (pin "A14") (pinfunction "A14_A14") (pintype "bidirectional"))
    )
    (net (code "115") (name "unconnected-(PCB1-PadA15)") (class "Default")
      (node (ref "PCB1") (pin "A15") (pinfunction "A15_A15") (pintype "bidirectional"))
    )
    (net (code "116") (name "unconnected-(PCB1-PadAREF)") (class "Default")
      (node (ref "PCB1") (pin "AREF") (pinfunction "AREF_AREF") (pintype "bidirectional"))
    )
    (net (code "117") (name "unconnected-(PCB1-PadGND)") (class "Default")
      (node (ref "PCB1") (pin "GND") (pinfunction "GND_GND") (pintype "bidirectional"))
    )
    (net (code "118") (name "unconnected-(PCB1-PadGND.)") (class "Default")
      (node (ref "PCB1") (pin "GND.") (pinfunction "GND._GND.") (pintype "bidirectional"))
    )
    (net (code "119") (name "unconnected-(PCB1-PadGND..)") (class "Default")
      (node (ref "PCB1") (pin "GND..") (pinfunction "GND.._GND..") (pintype "bidirectional"))
    )
    (net (code "120") (name "unconnected-(PCB1-PadGND...)") (class "Default")
      (node (ref "PCB1") (pin "GND...") (pinfunction "GND..._GND...") (pintype "bidirectional"))
    )
    (net (code "121") (name "unconnected-(PCB1-PadGND....)") (class "Default")
      (node (ref "PCB1") (pin "GND....") (pinfunction "GND...._GND....") (pintype "bidirectional"))
    )
    (net (code "122") (name "unconnected-(PCB1-PadGND__)") (class "Default")
      (node (ref "PCB1") (pin "GND__") (pinfunction "GND___GND__") (pintype "bidirectional"))
    )
    (net (code "123") (name "unconnected-(PCB1-PadMISO)") (class "Default")
      (node (ref "PCB1") (pin "MISO") (pinfunction "MISO_MISO") (pintype "bidirectional"))
    )
    (net (code "124") (name "unconnected-(PCB1-PadMOSI)") (class "Default")
      (node (ref "PCB1") (pin "MOSI") (pinfunction "MOSI_MOSI") (pintype "bidirectional"))
    )
    (net (code "125") (name "unconnected-(PCB1-PadRESET)") (class "Default")
      (node (ref "PCB1") (pin "RESET") (pinfunction "RESET_RESET") (pintype "bidirectional"))
    )
    (net (code "126") (name "unconnected-(PCB1-PadRESET.)") (class "Default")
      (node (ref "PCB1") (pin "RESET.") (pinfunction "RESET._RESET.") (pintype "bidirectional"))
    )
    (net (code "127") (name "unconnected-(PCB1-PadSCK)") (class "Default")
      (node (ref "PCB1") (pin "SCK") (pinfunction "SCK_SCK") (pintype "bidirectional"))
    )
    (net (code "128") (name "unconnected-(PCB1-PadSCL1)") (class "Default")
      (node (ref "PCB1") (pin "SCL1") (pinfunction "SCL1_SCL1") (pintype "bidirectional"))
    )
    (net (code "129") (name "unconnected-(PCB1-PadSDA1)") (class "Default")
      (node (ref "PCB1") (pin "SDA1") (pinfunction "SDA1_SDA1") (pintype "bidirectional"))
    )
    (net (code "130") (name "unconnected-(PCB1-PadVIN)") (class "Default")
      (node (ref "PCB1") (pin "VIN") (pinfunction "VIN_VIN") (pintype "bidirectional"))
    )
    (net (code "131") (name "unconnected-(X1-Pad4)") (class "Default")
      (node (ref "X1") (pin "4") (pinfunction "4_4") (pintype "passive"))
    )
    (net (code "132") (name "unconnected-(X2-Pad4)") (class "Default")
      (node (ref "X2") (pin "4") (pinfunction "4_4") (pintype "passive"))
    )
    (net (code "133") (name "unconnected-(X3-Pad4)") (class "Default")
      (node (ref "X3") (pin "4") (pinfunction "4_4") (pintype "passive"))
    )
    (net (code "134") (name "unconnected-(X4-Pad4)") (class "Default")
      (node (ref "X4") (pin "4") (pinfunction "4_4") (pintype "passive"))
    )
    (net (code "135") (name "unconnected-(X5-Pad4)") (class "Default")
      (node (ref "X5") (pin "4") (pinfunction "4_4") (pintype "passive"))
    )
    (net (code "136") (name "unconnected-(X6-Pad4)") (class "Default")
      (node (ref "X6") (pin "4") (pinfunction "4_4") (pintype "passive"))
    )
    (net (code "137") (name "unconnected-(X7-Pad4)") (class "Default")
      (node (ref "X7") (pin "4") (pinfunction "4_4") (pintype "passive"))
    )
    (net (code "138") (name "unconnected-(X8-Pad4)") (class "Default")
      (node (ref "X8") (pin "4") (pinfunction "4_4") (pintype "passive"))
    )
    (net (code "139") (name "unconnected-(X9-Pad4)") (class "Default")
      (node (ref "X9") (pin "4") (pinfunction "4_4") (pintype "passive"))
    )
    (net (code "140") (name "unconnected-(X10-Pad4)") (class "Default")
      (node (ref "X10") (pin "4") (pinfunction "4_4") (pintype "passive"))
    )
  )
)
